# schematic.net
KiCad netlist of a schematic drawn in EAGLE
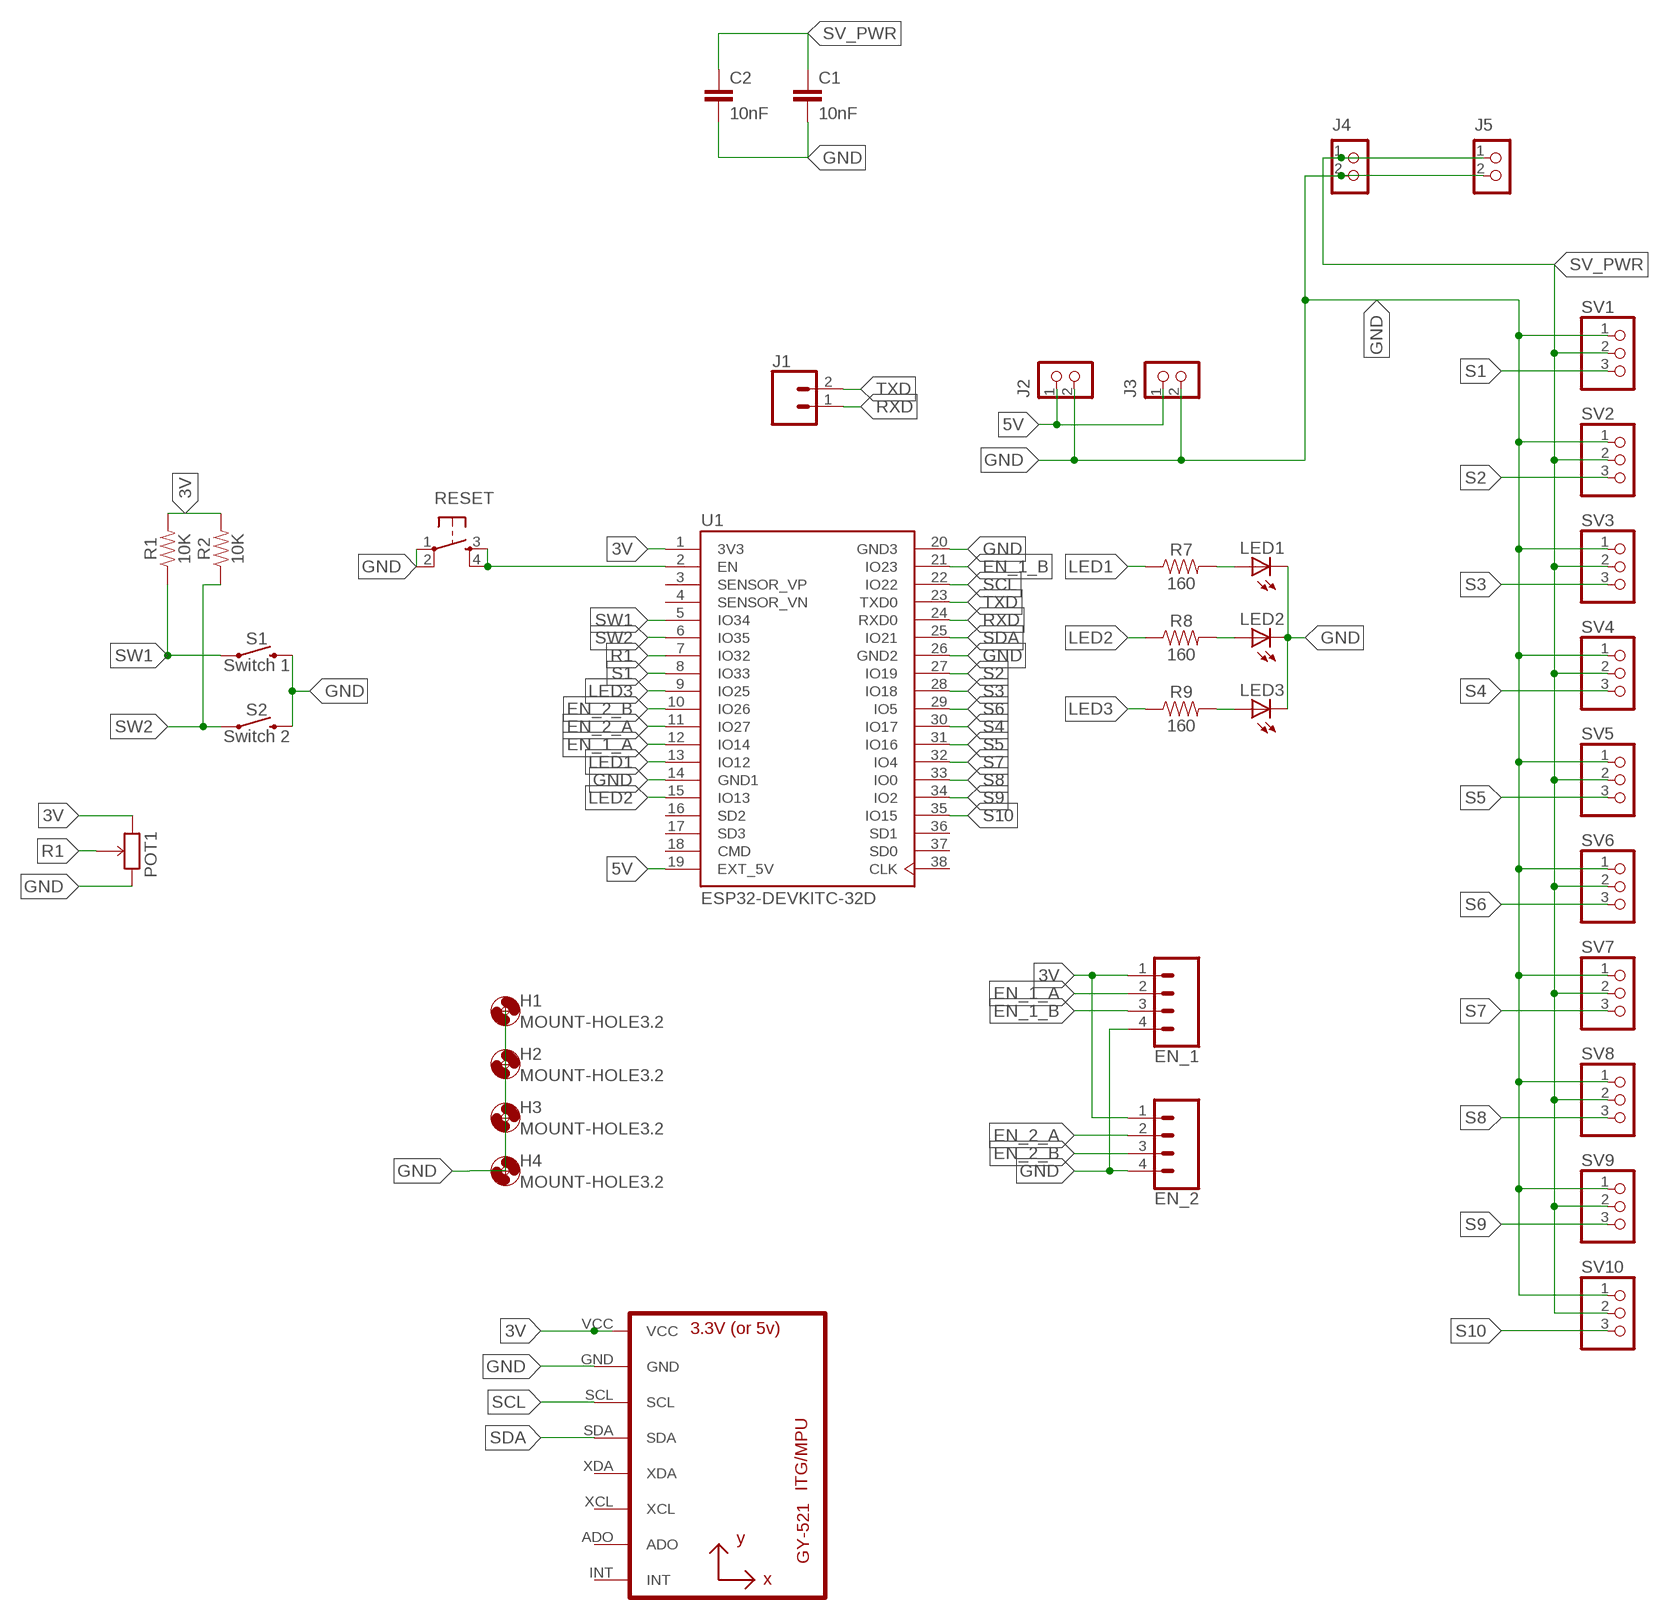
[diagram p0: schematic, sheet 1]

(export (version "E")
  (design (tool "Eeschema 10.0.6"))
  (components
    (comp (ref "C1")
      (value "10nF")
      (footprint "eagle-import:CAP-PTH-10MM")
      (libsource (lib "eagle-import") (part "10NF-PTH-10MM-10000V-1-%"))
    )
    (comp (ref "C2")
      (value "10nF")
      (footprint "eagle-import:CAP-PTH-10MM")
      (libsource (lib "eagle-import") (part "10NF-PTH-10MM-10000V-1-%"))
    )
    (comp (ref "EN_1")
      (value "CONN_04")
      (footprint "eagle-import:1X04")
      (libsource (lib "eagle-import") (part "CONN_04"))
    )
    (comp (ref "EN_2")
      (value "CONN_04")
      (footprint "eagle-import:1X04")
      (libsource (lib "eagle-import") (part "CONN_04"))
    )
    (comp (ref "H1")
      (value "MOUNT-HOLE3.2")
      (footprint "eagle-import:3,2")
      (libsource (lib "eagle-import") (part "MOUNT-HOLE3.2"))
    )
    (comp (ref "H2")
      (value "MOUNT-HOLE3.2")
      (footprint "eagle-import:3,2")
      (libsource (lib "eagle-import") (part "MOUNT-HOLE3.2"))
    )
    (comp (ref "H3")
      (value "MOUNT-HOLE3.2")
      (footprint "eagle-import:3,2")
      (libsource (lib "eagle-import") (part "MOUNT-HOLE3.2"))
    )
    (comp (ref "H4")
      (value "MOUNT-HOLE3.2")
      (footprint "eagle-import:3,2")
      (libsource (lib "eagle-import") (part "MOUNT-HOLE3.2"))
    )
    (comp (ref "J1")
      (value "CONN_02")
      (footprint "eagle-import:1X02")
      (libsource (lib "eagle-import") (part "CONN_02"))
    )
    (comp (ref "J2")
      (value "CON_TERMINAL_BLOCK_02-5MM")
      (footprint "eagle-import:TERMINAL_BLOCK_2P_5")
      (libsource (lib "eagle-import") (part "CON_TERMINAL_BLOCK_02-5MM"))
    )
    (comp (ref "J3")
      (value "CON_TERMINAL_BLOCK_02-5MM")
      (footprint "eagle-import:TERMINAL_BLOCK_2P_5")
      (libsource (lib "eagle-import") (part "CON_TERMINAL_BLOCK_02-5MM"))
    )
    (comp (ref "J4")
      (value "CON_TERMINAL_BLOCK_02-5MM")
      (footprint "eagle-import:TERMINAL_BLOCK_2P_5")
      (libsource (lib "eagle-import") (part "CON_TERMINAL_BLOCK_02-5MM"))
    )
    (comp (ref "J5")
      (value "CON_TERMINAL_BLOCK_02-5MM")
      (footprint "eagle-import:TERMINAL_BLOCK_2P_5")
      (libsource (lib "eagle-import") (part "CON_TERMINAL_BLOCK_02-5MM"))
    )
    (comp (ref "LED1")
      (value "LED3MM")
      (footprint "eagle-import:LED3MM")
      (libsource (lib "eagle-import") (part "LED3MM"))
    )
    (comp (ref "LED2")
      (value "LED3MM")
      (footprint "eagle-import:LED3MM")
      (libsource (lib "eagle-import") (part "LED3MM"))
    )
    (comp (ref "LED3")
      (value "LED3MM")
      (footprint "eagle-import:LED3MM")
      (libsource (lib "eagle-import") (part "LED3MM"))
    )
    (comp (ref "POT1")
      (value "POTENTIOMETER_THT")
      (footprint "eagle-import:POTENTIOMETER")
      (libsource (lib "eagle-import") (part "POTENTIOMETER_THT"))
    )
    (comp (ref "R1")
      (value "10K")
      (footprint "eagle-import:AXIAL-0.3")
      (libsource (lib "eagle-import") (part "10KOHM-HORIZ-1/4W-1%"))
    )
    (comp (ref "R2")
      (value "10K")
      (footprint "eagle-import:AXIAL-0.3")
      (libsource (lib "eagle-import") (part "10KOHM-HORIZ-1/4W-1%"))
    )
    (comp (ref "R7")
      (value "160")
      (footprint "eagle-import:AXIAL-0.3")
      (libsource (lib "eagle-import") (part "10KOHM-HORIZ-1/4W-1%"))
    )
    (comp (ref "R8")
      (value "160")
      (footprint "eagle-import:AXIAL-0.3")
      (libsource (lib "eagle-import") (part "10KOHM-HORIZ-1/4W-1%"))
    )
    (comp (ref "R9")
      (value "160")
      (footprint "eagle-import:AXIAL-0.3")
      (libsource (lib "eagle-import") (part "10KOHM-HORIZ-1/4W-1%"))
    )
    (comp (ref "RESET")
      (value "TAC_SWITCHPTH")
      (footprint "eagle-import:TACTILE-PTH")
      (libsource (lib "eagle-import") (part "TAC_SWITCHPTH"))
    )
    (comp (ref "S1")
      (value "Switch 1")
      (footprint "eagle-import:TACTILE_SWITCH_PTH_12MM")
      (libsource (lib "eagle-import") (part "MOMENTARY-SWITCH-SPST-PTH-12MM"))
    )
    (comp (ref "S2")
      (value "Switch 2")
      (footprint "eagle-import:TACTILE_SWITCH_PTH_12MM")
      (libsource (lib "eagle-import") (part "MOMENTARY-SWITCH-SPST-PTH-12MM"))
    )
    (comp (ref "SV1")
      (value "PINHD-1X3")
      (footprint "eagle-import:1X03")
      (libsource (lib "eagle-import") (part "PINHD-1X3"))
    )
    (comp (ref "SV2")
      (value "PINHD-1X3")
      (footprint "eagle-import:1X03")
      (libsource (lib "eagle-import") (part "PINHD-1X3"))
    )
    (comp (ref "SV3")
      (value "PINHD-1X3")
      (footprint "eagle-import:1X03")
      (libsource (lib "eagle-import") (part "PINHD-1X3"))
    )
    (comp (ref "SV4")
      (value "PINHD-1X3")
      (footprint "eagle-import:1X03")
      (libsource (lib "eagle-import") (part "PINHD-1X3"))
    )
    (comp (ref "SV5")
      (value "PINHD-1X3")
      (footprint "eagle-import:1X03")
      (libsource (lib "eagle-import") (part "PINHD-1X3"))
    )
    (comp (ref "SV6")
      (value "PINHD-1X3")
      (footprint "eagle-import:1X03")
      (libsource (lib "eagle-import") (part "PINHD-1X3"))
    )
    (comp (ref "SV7")
      (value "PINHD-1X3")
      (footprint "eagle-import:1X03")
      (libsource (lib "eagle-import") (part "PINHD-1X3"))
    )
    (comp (ref "SV8")
      (value "PINHD-1X3")
      (footprint "eagle-import:1X03")
      (libsource (lib "eagle-import") (part "PINHD-1X3"))
    )
    (comp (ref "SV9")
      (value "PINHD-1X3")
      (footprint "eagle-import:1X03")
      (libsource (lib "eagle-import") (part "PINHD-1X3"))
    )
    (comp (ref "SV10")
      (value "PINHD-1X3")
      (footprint "eagle-import:1X03")
      (libsource (lib "eagle-import") (part "PINHD-1X3"))
    )
    (comp (ref "U1")
      (value "ESP32-DEVKITC-32D")
      (footprint "eagle-import:MODULE_ESP32-DEVKITC-32D")
      (fields (field (name "MF") "Espressif Systems"))
      (libsource (lib "eagle-import") (part "ESP32-DEVKITC-32D"))
    )
    (comp (ref "U2")
      (value "GY-521MPU6050")
      (footprint "eagle-import:GY-521")
      (libsource (lib "eagle-import") (part "GY-521MPU6050"))
    )
  )
  (nets
    (net (code "1") (name "3V") (class "Default")
      (node (ref "EN_1") (pin "1") (pinfunction "1_1") (pintype "passive"))
      (node (ref "EN_2") (pin "1") (pinfunction "1_1") (pintype "passive"))
      (node (ref "POT1") (pin "3") (pinfunction "CW_3") (pintype "passive"))
      (node (ref "R1") (pin "P$2") (pinfunction "2_P$2") (pintype "passive"))
      (node (ref "R2") (pin "P$2") (pinfunction "2_P$2") (pintype "passive"))
      (node (ref "U1") (pin "1") (pinfunction "3V3_1") (pintype "power_in"))
      (node (ref "U2") (pin "VCC") (pinfunction "VCC_VCC") (pintype "bidirectional"))
    )
    (net (code "2") (name "5V") (class "Default")
      (node (ref "J2") (pin "1") (pinfunction "1_1") (pintype "passive"))
      (node (ref "J3") (pin "1") (pinfunction "1_1") (pintype "passive"))
      (node (ref "U1") (pin "19") (pinfunction "EXT_5V_19") (pintype "power_in"))
    )
    (net (code "3") (name "EN_1_A") (class "Default")
      (node (ref "EN_1") (pin "2") (pinfunction "2_2") (pintype "passive"))
      (node (ref "U1") (pin "12") (pinfunction "IO14_12") (pintype "bidirectional"))
    )
    (net (code "4") (name "EN_1_B") (class "Default")
      (node (ref "EN_1") (pin "3") (pinfunction "3_3") (pintype "passive"))
      (node (ref "U1") (pin "21") (pinfunction "IO23_21") (pintype "bidirectional"))
    )
    (net (code "5") (name "EN_2_A") (class "Default")
      (node (ref "EN_2") (pin "2") (pinfunction "2_2") (pintype "passive"))
      (node (ref "U1") (pin "11") (pinfunction "IO27_11") (pintype "bidirectional"))
    )
    (net (code "6") (name "EN_2_B") (class "Default")
      (node (ref "EN_2") (pin "3") (pinfunction "3_3") (pintype "passive"))
      (node (ref "U1") (pin "10") (pinfunction "IO26_10") (pintype "bidirectional"))
    )
    (net (code "7") (name "GND") (class "Default")
      (node (ref "C1") (pin "2") (pinfunction "2_2") (pintype "passive"))
      (node (ref "C2") (pin "2") (pinfunction "2_2") (pintype "passive"))
      (node (ref "EN_1") (pin "4") (pinfunction "4_4") (pintype "passive"))
      (node (ref "EN_2") (pin "4") (pinfunction "4_4") (pintype "passive"))
      (node (ref "J2") (pin "2") (pinfunction "2_2") (pintype "passive"))
      (node (ref "J3") (pin "2") (pinfunction "2_2") (pintype "passive"))
      (node (ref "J4") (pin "2") (pinfunction "2_2") (pintype "passive"))
      (node (ref "J5") (pin "2") (pinfunction "2_2") (pintype "passive"))
      (node (ref "LED1") (pin "K") (pinfunction "C_K") (pintype "passive"))
      (node (ref "LED2") (pin "K") (pinfunction "C_K") (pintype "passive"))
      (node (ref "LED3") (pin "K") (pinfunction "C_K") (pintype "passive"))
      (node (ref "POT1") (pin "1") (pinfunction "CCW_1") (pintype "passive"))
      (node (ref "RESET") (pin "1") (pinfunction "1_1") (pintype "passive"))
      (node (ref "RESET") (pin "2") (pinfunction "2_2") (pintype "passive"))
      (node (ref "S1") (pin "3") (pinfunction "2_3") (pintype "passive"))
      (node (ref "S2") (pin "3") (pinfunction "2_3") (pintype "passive"))
      (node (ref "SV1") (pin "1") (pinfunction "1_1") (pintype "passive"))
      (node (ref "SV10") (pin "1") (pinfunction "1_1") (pintype "passive"))
      (node (ref "SV2") (pin "1") (pinfunction "1_1") (pintype "passive"))
      (node (ref "SV3") (pin "1") (pinfunction "1_1") (pintype "passive"))
      (node (ref "SV4") (pin "1") (pinfunction "1_1") (pintype "passive"))
      (node (ref "SV5") (pin "1") (pinfunction "1_1") (pintype "passive"))
      (node (ref "SV6") (pin "1") (pinfunction "1_1") (pintype "passive"))
      (node (ref "SV7") (pin "1") (pinfunction "1_1") (pintype "passive"))
      (node (ref "SV8") (pin "1") (pinfunction "1_1") (pintype "passive"))
      (node (ref "SV9") (pin "1") (pinfunction "1_1") (pintype "passive"))
      (node (ref "U1") (pin "14") (pinfunction "GND1_14") (pintype "power_in"))
      (node (ref "U1") (pin "20") (pinfunction "GND3_20") (pintype "power_in"))
      (node (ref "U1") (pin "26") (pinfunction "GND2_26") (pintype "power_in"))
      (node (ref "U2") (pin "GND") (pinfunction "GND_GND") (pintype "bidirectional"))
    )
    (net (code "8") (name "LED1") (class "Default")
      (node (ref "R7") (pin "P$1") (pinfunction "1_P$1") (pintype "passive"))
      (node (ref "U1") (pin "13") (pinfunction "IO12_13") (pintype "bidirectional"))
    )
    (net (code "9") (name "LED2") (class "Default")
      (node (ref "R8") (pin "P$1") (pinfunction "1_P$1") (pintype "passive"))
      (node (ref "U1") (pin "15") (pinfunction "IO13_15") (pintype "bidirectional"))
    )
    (net (code "10") (name "LED3") (class "Default")
      (node (ref "R9") (pin "P$1") (pinfunction "1_P$1") (pintype "passive"))
      (node (ref "U1") (pin "9") (pinfunction "IO25_9") (pintype "bidirectional"))
    )
    (net (code "11") (name "Net-(R7-2)") (class "Default")
      (node (ref "LED1") (pin "A") (pinfunction "A_A") (pintype "passive"))
      (node (ref "R7") (pin "P$2") (pinfunction "2_P$2") (pintype "passive"))
    )
    (net (code "12") (name "Net-(R8-2)") (class "Default")
      (node (ref "LED2") (pin "A") (pinfunction "A_A") (pintype "passive"))
      (node (ref "R8") (pin "P$2") (pinfunction "2_P$2") (pintype "passive"))
    )
    (net (code "13") (name "Net-(R9-2)") (class "Default")
      (node (ref "LED3") (pin "A") (pinfunction "A_A") (pintype "passive"))
      (node (ref "R9") (pin "P$2") (pinfunction "2_P$2") (pintype "passive"))
    )
    (net (code "14") (name "Net-(U1-EN)") (class "Default")
      (node (ref "RESET") (pin "3") (pinfunction "3_3") (pintype "passive"))
      (node (ref "RESET") (pin "4") (pinfunction "4_4") (pintype "passive"))
      (node (ref "U1") (pin "2") (pinfunction "EN_2") (pintype "input"))
    )
    (net (code "15") (name "R1") (class "Default")
      (node (ref "POT1") (pin "2") (pinfunction "WIPER_2") (pintype "passive"))
      (node (ref "U1") (pin "7") (pinfunction "IO32_7") (pintype "bidirectional"))
    )
    (net (code "16") (name "RXD") (class "Default")
      (node (ref "J1") (pin "1") (pinfunction "1_1") (pintype "passive"))
      (node (ref "U1") (pin "24") (pinfunction "RXD0_24") (pintype "input"))
    )
    (net (code "17") (name "S1") (class "Default")
      (node (ref "SV1") (pin "3") (pinfunction "3_3") (pintype "passive"))
      (node (ref "U1") (pin "8") (pinfunction "IO33_8") (pintype "bidirectional"))
    )
    (net (code "18") (name "S2") (class "Default")
      (node (ref "SV2") (pin "3") (pinfunction "3_3") (pintype "passive"))
      (node (ref "U1") (pin "27") (pinfunction "IO19_27") (pintype "bidirectional"))
    )
    (net (code "19") (name "S3") (class "Default")
      (node (ref "SV3") (pin "3") (pinfunction "3_3") (pintype "passive"))
      (node (ref "U1") (pin "28") (pinfunction "IO18_28") (pintype "bidirectional"))
    )
    (net (code "20") (name "S4") (class "Default")
      (node (ref "SV4") (pin "3") (pinfunction "3_3") (pintype "passive"))
      (node (ref "U1") (pin "30") (pinfunction "IO17_30") (pintype "bidirectional"))
    )
    (net (code "21") (name "S5") (class "Default")
      (node (ref "SV5") (pin "3") (pinfunction "3_3") (pintype "passive"))
      (node (ref "U1") (pin "31") (pinfunction "IO16_31") (pintype "bidirectional"))
    )
    (net (code "22") (name "S6") (class "Default")
      (node (ref "SV6") (pin "3") (pinfunction "3_3") (pintype "passive"))
      (node (ref "U1") (pin "29") (pinfunction "IO5_29") (pintype "bidirectional"))
    )
    (net (code "23") (name "S7") (class "Default")
      (node (ref "SV7") (pin "3") (pinfunction "3_3") (pintype "passive"))
      (node (ref "U1") (pin "32") (pinfunction "IO4_32") (pintype "bidirectional"))
    )
    (net (code "24") (name "S8") (class "Default")
      (node (ref "SV8") (pin "3") (pinfunction "3_3") (pintype "passive"))
      (node (ref "U1") (pin "33") (pinfunction "IO0_33") (pintype "bidirectional"))
    )
    (net (code "25") (name "S9") (class "Default")
      (node (ref "SV9") (pin "3") (pinfunction "3_3") (pintype "passive"))
      (node (ref "U1") (pin "34") (pinfunction "IO2_34") (pintype "bidirectional"))
    )
    (net (code "26") (name "S10") (class "Default")
      (node (ref "SV10") (pin "3") (pinfunction "3_3") (pintype "passive"))
      (node (ref "U1") (pin "35") (pinfunction "IO15_35") (pintype "bidirectional"))
    )
    (net (code "27") (name "SCL") (class "Default")
      (node (ref "U1") (pin "22") (pinfunction "IO22_22") (pintype "bidirectional"))
      (node (ref "U2") (pin "SCL") (pinfunction "SCL_SCL") (pintype "bidirectional"))
    )
    (net (code "28") (name "SDA") (class "Default")
      (node (ref "U1") (pin "25") (pinfunction "IO21_25") (pintype "bidirectional"))
      (node (ref "U2") (pin "SDA") (pinfunction "SDA_SDA") (pintype "bidirectional"))
    )
    (net (code "29") (name "SV_PWR") (class "Default")
      (node (ref "C1") (pin "1") (pinfunction "1_1") (pintype "passive"))
      (node (ref "C2") (pin "1") (pinfunction "1_1") (pintype "passive"))
      (node (ref "J4") (pin "1") (pinfunction "1_1") (pintype "passive"))
      (node (ref "J5") (pin "1") (pinfunction "1_1") (pintype "passive"))
      (node (ref "SV1") (pin "2") (pinfunction "2_2") (pintype "passive"))
      (node (ref "SV10") (pin "2") (pinfunction "2_2") (pintype "passive"))
      (node (ref "SV2") (pin "2") (pinfunction "2_2") (pintype "passive"))
      (node (ref "SV3") (pin "2") (pinfunction "2_2") (pintype "passive"))
      (node (ref "SV4") (pin "2") (pinfunction "2_2") (pintype "passive"))
      (node (ref "SV5") (pin "2") (pinfunction "2_2") (pintype "passive"))
      (node (ref "SV6") (pin "2") (pinfunction "2_2") (pintype "passive"))
      (node (ref "SV7") (pin "2") (pinfunction "2_2") (pintype "passive"))
      (node (ref "SV8") (pin "2") (pinfunction "2_2") (pintype "passive"))
      (node (ref "SV9") (pin "2") (pinfunction "2_2") (pintype "passive"))
    )
    (net (code "30") (name "SW1") (class "Default")
      (node (ref "R1") (pin "P$1") (pinfunction "1_P$1") (pintype "passive"))
      (node (ref "S1") (pin "1") (pinfunction "1_1") (pintype "passive"))
      (node (ref "U1") (pin "5") (pinfunction "IO34_5") (pintype "bidirectional"))
    )
    (net (code "31") (name "SW2") (class "Default")
      (node (ref "R2") (pin "P$1") (pinfunction "1_P$1") (pintype "passive"))
      (node (ref "S2") (pin "1") (pinfunction "1_1") (pintype "passive"))
      (node (ref "U1") (pin "6") (pinfunction "IO35_6") (pintype "bidirectional"))
    )
    (net (code "32") (name "TXD") (class "Default")
      (node (ref "J1") (pin "2") (pinfunction "2_2") (pintype "passive"))
      (node (ref "U1") (pin "23") (pinfunction "TXD0_23") (pintype "output"))
    )
    (net (code "33") (name "unconnected-(U1-CLK-Pad38)") (class "Default")
      (node (ref "U1") (pin "38") (pinfunction "CLK_38") (pintype "input"))
    )
    (net (code "34") (name "unconnected-(U1-CMD-Pad18)") (class "Default")
      (node (ref "U1") (pin "18") (pinfunction "CMD_18") (pintype "bidirectional"))
    )
    (net (code "35") (name "unconnected-(U1-SD0-Pad37)") (class "Default")
      (node (ref "U1") (pin "37") (pinfunction "SD0_37") (pintype "bidirectional"))
    )
    (net (code "36") (name "unconnected-(U1-SD1-Pad36)") (class "Default")
      (node (ref "U1") (pin "36") (pinfunction "SD1_36") (pintype "bidirectional"))
    )
    (net (code "37") (name "unconnected-(U1-SD2-Pad16)") (class "Default")
      (node (ref "U1") (pin "16") (pinfunction "SD2_16") (pintype "bidirectional"))
    )
    (net (code "38") (name "unconnected-(U1-SD3-Pad17)") (class "Default")
      (node (ref "U1") (pin "17") (pinfunction "SD3_17") (pintype "bidirectional"))
    )
    (net (code "39") (name "unconnected-(U1-SENSOR_VN-Pad4)") (class "Default")
      (node (ref "U1") (pin "4") (pinfunction "SENSOR_VN_4") (pintype "input"))
    )
    (net (code "40") (name "unconnected-(U1-SENSOR_VP-Pad3)") (class "Default")
      (node (ref "U1") (pin "3") (pinfunction "SENSOR_VP_3") (pintype "input"))
    )
    (net (code "41") (name "unconnected-(U2-PadADO)") (class "Default")
      (node (ref "U2") (pin "ADO") (pinfunction "ADO_ADO") (pintype "bidirectional"))
    )
    (net (code "42") (name "unconnected-(U2-PadINT)") (class "Default")
      (node (ref "U2") (pin "INT") (pinfunction "INT_INT") (pintype "bidirectional"))
    )
    (net (code "43") (name "unconnected-(U2-PadXCL)") (class "Default")
      (node (ref "U2") (pin "XCL") (pinfunction "XCL_XCL") (pintype "bidirectional"))
    )
    (net (code "44") (name "unconnected-(U2-PadXDA)") (class "Default")
      (node (ref "U2") (pin "XDA") (pinfunction "XDA_XDA") (pintype "bidirectional"))
    )
  )
)
